# schematic.net
KiCad netlist of a schematic drawn in EAGLE
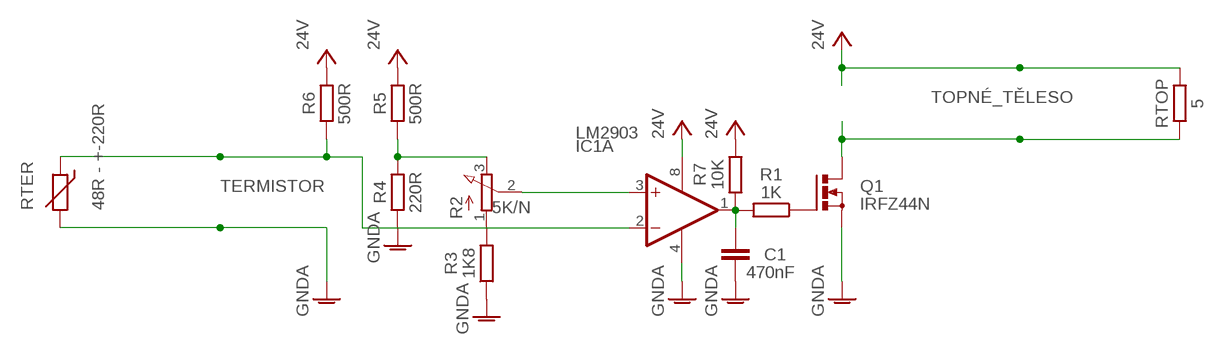
[diagram p0: schematic, sheet 1]

(export (version "E")
  (design (tool "Eeschema 10.0.6"))
  (components
    (comp (ref "C1")
      (value "470nF")
      (footprint "eagle-import:C2.5-2")
      (libsource (lib "eagle-import") (part "C2.5/2"))
    )
    (comp (ref "IC1")
      (value "LM2903")
      (footprint "eagle-import:DIL08")
      (libsource (lib "eagle-import") (part "LM358N"))
    )
    (comp (ref "Q1")
      (value "IRFZ44N")
      (footprint "eagle-import:TO220BH")
      (fields (field (name "SPICEPREFIX") "M"))
      (libsource (lib "eagle-import") (part "PMOSFET_NTO220BH"))
    )
    (comp (ref "R1")
      (value "1K")
      (footprint "eagle-import:RESAD724W46L381D178B")
      (fields (field (name "SPICEPREFIX") "R"))
      (libsource (lib "eagle-import") (part "RAXIAL-7.2MM-PITCH_"))
    )
    (comp (ref "R2")
      (value "5K/N")
      (footprint "eagle-import:3RP_1610N")
      (fields (field (name "SPICEPREFIX") "J"))
      (libsource (lib "eagle-import") (part "3RP/1610N"))
    )
    (comp (ref "R3")
      (value "1K8")
      (footprint "eagle-import:RESAD724W46L381D178B")
      (fields (field (name "SPICEPREFIX") "R"))
      (libsource (lib "eagle-import") (part "RAXIAL-7.2MM-PITCH_"))
    )
    (comp (ref "R4")
      (value "220R")
      (footprint "eagle-import:RESAD724W46L381D178B")
      (fields (field (name "SPICEPREFIX") "R"))
      (libsource (lib "eagle-import") (part "RAXIAL-7.2MM-PITCH_"))
    )
    (comp (ref "R5")
      (value "500R")
      (footprint "eagle-import:RESAD724W46L381D178B")
      (fields (field (name "SPICEPREFIX") "R"))
      (libsource (lib "eagle-import") (part "RAXIAL-7.2MM-PITCH_"))
    )
    (comp (ref "R6")
      (value "500R")
      (footprint "eagle-import:RESAD724W46L381D178B")
      (fields (field (name "SPICEPREFIX") "R"))
      (libsource (lib "eagle-import") (part "RAXIAL-7.2MM-PITCH_"))
    )
    (comp (ref "R7")
      (value "10K")
      (footprint "eagle-import:RESAD724W46L381D178B")
      (fields (field (name "SPICEPREFIX") "R"))
      (libsource (lib "eagle-import") (part "RAXIAL-7.2MM-PITCH_"))
    )
    (comp (ref "RTER")
      (value "48R - +-220R")
      (footprint "eagle-import:RS-2,5")
      (libsource (lib "eagle-import") (part "THERMISTOR-2,5"))
    )
    (comp (ref "RTOP")
      (value "5")
      (footprint "eagle-import:RESAD724W46L381D178B")
      (fields (field (name "SPICEPREFIX") "R"))
      (libsource (lib "eagle-import") (part "RAXIAL-7.2MM-PITCH_"))
    )
  )
  (nets
    (net (code "1") (name "/TERMISTOR") (class "Default")
      (node (ref "IC1") (pin "2") (pinfunction "-IN_2") (pintype "input"))
      (node (ref "R6") (pin "1") (pinfunction "1_1") (pintype "passive"))
      (node (ref "RTER") (pin "1") (pinfunction "1_1") (pintype "passive"))
    )
    (net (code "2") (name "/TOPNÉ_TĚLESO") (class "Default")
      (node (ref "Q1") (pin "D") (pinfunction "D_D") (pintype "passive"))
      (node (ref "RTOP") (pin "1") (pinfunction "1_1") (pintype "passive"))
    )
    (net (code "3") (name "24V") (class "Default")
      (node (ref "IC1") (pin "8") (pinfunction "V+_8") (pintype "power_in"))
      (node (ref "R5") (pin "2") (pinfunction "2_2") (pintype "passive"))
      (node (ref "R6") (pin "2") (pinfunction "2_2") (pintype "passive"))
      (node (ref "R7") (pin "1") (pinfunction "1_1") (pintype "passive"))
      (node (ref "RTOP") (pin "2") (pinfunction "2_2") (pintype "passive"))
    )
    (net (code "4") (name "GNDA") (class "Default")
      (node (ref "C1") (pin "2") (pinfunction "2_2") (pintype "passive"))
      (node (ref "IC1") (pin "4") (pinfunction "V-_4") (pintype "power_in"))
      (node (ref "Q1") (pin "S") (pinfunction "S_S") (pintype "passive"))
      (node (ref "R3") (pin "1") (pinfunction "1_1") (pintype "passive"))
      (node (ref "R4") (pin "1") (pinfunction "1_1") (pintype "passive"))
      (node (ref "RTER") (pin "2") (pinfunction "2_2") (pintype "passive"))
    )
    (net (code "5") (name "Net-(IC1A-+IN)") (class "Default")
      (node (ref "IC1") (pin "3") (pinfunction "+IN_3") (pintype "input"))
      (node (ref "R2") (pin "2") (pinfunction "S_2") (pintype "passive"))
    )
    (net (code "6") (name "Net-(IC1A-OUT)") (class "Default")
      (node (ref "C1") (pin "1") (pinfunction "1_1") (pintype "passive"))
      (node (ref "IC1") (pin "1") (pinfunction "OUT_1") (pintype "output"))
      (node (ref "R1") (pin "2") (pinfunction "2_2") (pintype "passive"))
      (node (ref "R7") (pin "2") (pinfunction "2_2") (pintype "passive"))
    )
    (net (code "7") (name "Net-(Q1-PadG)") (class "Default")
      (node (ref "Q1") (pin "G") (pinfunction "G_G") (pintype "passive"))
      (node (ref "R1") (pin "1") (pinfunction "1_1") (pintype "passive"))
    )
    (net (code "8") (name "Net-(R2-A)") (class "Default")
      (node (ref "R2") (pin "1") (pinfunction "A_1") (pintype "passive"))
      (node (ref "R3") (pin "2") (pinfunction "2_2") (pintype "passive"))
    )
    (net (code "9") (name "Net-(R2-E)") (class "Default")
      (node (ref "R2") (pin "3") (pinfunction "E_3") (pintype "passive"))
      (node (ref "R4") (pin "2") (pinfunction "2_2") (pintype "passive"))
      (node (ref "R5") (pin "1") (pinfunction "1_1") (pintype "passive"))
    )
  )
)
